# Sata.net
KiCad netlist of a schematic drawn in Altium Designer
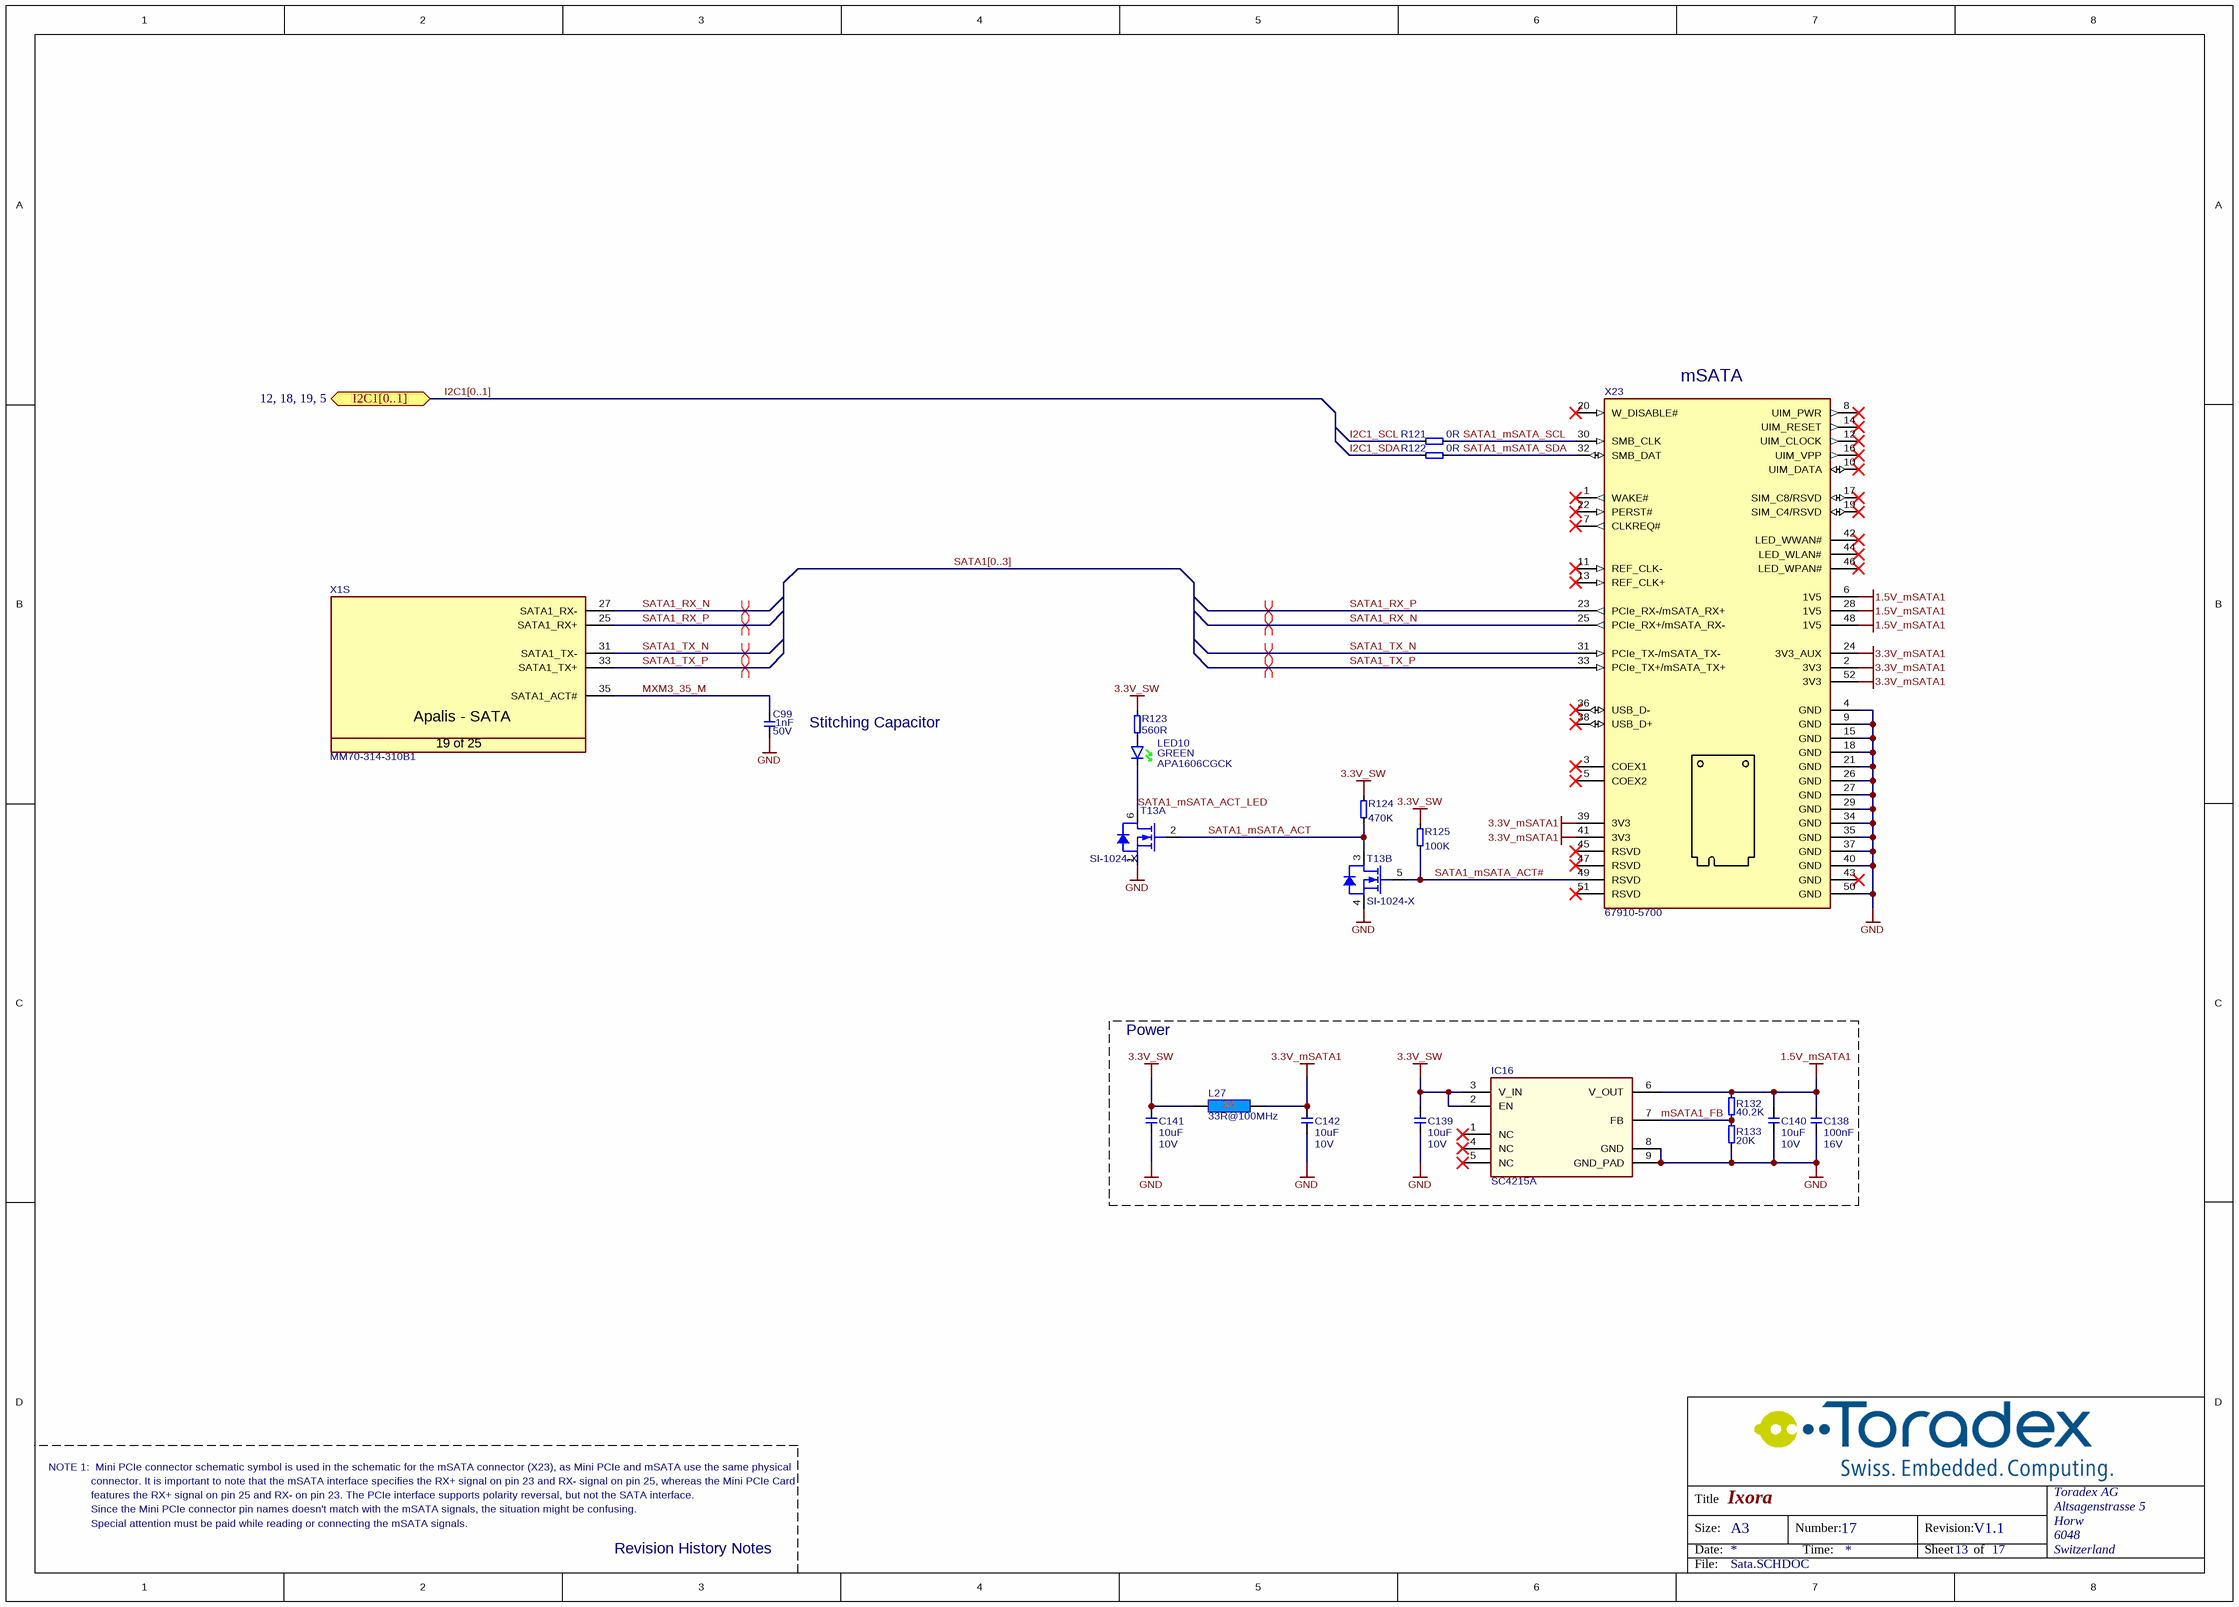
[diagram p0: Sata.SCHDOC]

(export (version "E")
  (design (tool "Eeschema 10.0.6"))
  (components
    (comp (ref "C99")
      (value "1nF")
      (footprint "CAPC1005X60N")
      (description "Capacitor Ceramic X7R 1nF 50V 10% 0402")
      (fields (field (name "TOLERANCE") "10%") (field (name "RATING") "50V"))
      (libsource (lib "Ixora") (part "C-X7R-1nF-50V-10%-0402"))
    )
    (comp (ref "C138")
      (value "100nF")
      (footprint "CAPC1005X60N")
      (description "Capacitor Ceramic X7R 100nF 16V 10% 0402")
      (fields (field (name "TOLERANCE") "10%") (field (name "RATING") "16V"))
      (libsource (lib "Ixora") (part "C-X7R-100nF-16V-10%-0402"))
    )
    (comp (ref "C139")
      (value "10uF")
      (footprint "T_CAPC0603X33N")
      (description "Capacitor Ceramic X5R 10uF 10V 20% 0603")
      (fields (field (name "TOLERANCE") "20%") (field (name "RATING") "10V"))
      (libsource (lib "Ixora") (part "C-X5R-10uF-10V-20%-0603"))
    )
    (comp (ref "C140")
      (value "10uF")
      (footprint "T_CAPC0603X33N")
      (description "Capacitor Ceramic X5R 10uF 10V 20% 0603")
      (fields (field (name "TOLERANCE") "20%") (field (name "RATING") "10V"))
      (libsource (lib "Ixora") (part "C-X5R-10uF-10V-20%-0603"))
    )
    (comp (ref "C141")
      (value "10uF")
      (footprint "T_CAPC0603X33N")
      (description "Capacitor Ceramic X5R 10uF 10V 20% 0603")
      (fields (field (name "TOLERANCE") "20%") (field (name "RATING") "10V"))
      (libsource (lib "Ixora") (part "C-X5R-10uF-10V-20%-0603"))
    )
    (comp (ref "C142")
      (value "10uF")
      (footprint "T_CAPC0603X33N")
      (description "Capacitor Ceramic X5R 10uF 10V 20% 0603")
      (fields (field (name "TOLERANCE") "20%") (field (name "RATING") "10V"))
      (libsource (lib "Ixora") (part "C-X5R-10uF-10V-20%-0603"))
    )
    (comp (ref "IC16")
      (value "IC-Semtech-SC4215A")
      (footprint "SOIC127P650X175_HS-8N")
      (description "LDO TO 2A")
      (fields (field (name "MANUFACTURER PART NO.") "SC4215A"))
      (libsource (lib "Ixora") (part "IC-Semtech-SC4215A"))
    )
    (comp (ref "L27")
      (value "33R@100MHz")
      (footprint "INDC1608X95N")
      (description "33R@100MHz 3A EMI FILTER")
      (fields (field (name "TOLERANCE") "25%"))
      (libsource (lib "Ixora") (part "L-33R@100MHz-3A-25%-0603"))
    )
    (comp (ref "LED10")
      (value "APA1606CGCK")
      (footprint "T_Kingbright_APA1606CGCK")
      (description "LED green Kingbright APA1606CGCK")
      (fields (field (name "COLOR") "GREEN") (field (name "MANUFACTURER PART NO.") "APA1606CGCK"))
      (libsource (lib "Ixora") (part "LED-Kingbright-APA1606CGCK"))
    )
    (comp (ref "R121")
      (value "0R")
      (footprint "RESC1005X40N")
      (description "Resistor 0 ohm 63mW 1% 0402")
      (fields (field (name "TOLERANCE") "1%"))
      (libsource (lib "Ixora") (part "R-0R-63mW-1%-0402"))
    )
    (comp (ref "R122")
      (value "0R")
      (footprint "RESC1005X40N")
      (description "Resistor 0 ohm 63mW 1% 0402")
      (fields (field (name "TOLERANCE") "1%"))
      (libsource (lib "Ixora") (part "R-0R-63mW-1%-0402"))
    )
    (comp (ref "R123")
      (value "560R")
      (footprint "RESC1005X40N")
      (description "Resistor 560 ohm 63mW 5% 0402")
      (fields (field (name "TOLERANCE") "5%"))
      (libsource (lib "Ixora") (part "R-560R-63mW-5%-0402"))
    )
    (comp (ref "R124")
      (value "470K")
      (footprint "RESC1005X40N")
      (description "Resistor 470 Kohm 63mW 5% 0402")
      (fields (field (name "TOLERANCE") "5%"))
      (libsource (lib "Ixora") (part "R-470KR-63mW-5%-0402"))
    )
    (comp (ref "R125")
      (value "100K")
      (footprint "RESC1005X40N")
      (description "Resistor 100 Kohm 63mW 5% 0402")
      (fields (field (name "TOLERANCE") "5%"))
      (libsource (lib "Ixora") (part "R-100KR-63mW-5%-0402"))
    )
    (comp (ref "R132")
      (value "40.2K")
      (footprint "RESC1005X40N")
      (description "Resistor 40.2 Kohm 63mW 1% 0402")
      (fields (field (name "TOLERANCE") "1%"))
      (libsource (lib "Ixora") (part "R-40.2KR-63mW-1%-0402"))
    )
    (comp (ref "R133")
      (value "20K")
      (footprint "RESC1005X40N")
      (description "Resistor 20 Kohm 63mW 1% 0402")
      (fields (field (name "TOLERANCE") "1%"))
      (libsource (lib "Ixora") (part "R-20KR-63mW-1%-0402"))
    )
    (comp (ref "T13")
      (value "T-Vishay-SI-1024X-N")
      (footprint "SOTFL50P160X60-6N")
      (description "Dual N-Channel 20V (D-S)  MOSFET")
      (fields (field (name "MANUFACTURER PART NO.") "SI-1024-X"))
      (libsource (lib "Ixora") (part "T-Vishay-SI-1024X-N"))
    )
    (comp (ref "X1")
      (value "CON-JAE-MM70-314-310B1-314-0.5mm")
      (footprint "T_JAE_MM70-314-310B1")
      (description "MXM3 Connector")
      (fields (field (name "MANUFACTURER PART NO.") "MM70-314-310B1"))
      (libsource (lib "Ixora") (part "CON-JAE-MM70-314-310B1-314-0.5mm"))
    )
    (comp (ref "X23")
      (value "67910-5700")
      (footprint "T_Molex_67910-5700")
      (description "PCIe_Mini Card Holder")
      (fields (field (name "PART NO.") "67910-5700"))
      (libsource (lib "Ixora") (part "CON-Molex-67910-5700"))
    )
  )
  (nets
    (net (code "8") (name "/I2C1_SCL") (class "Default")
      (node (ref "R121") (pin "1") (pinfunction "1_1") (pintype "passive"))
    )
    (net (code "9") (name "/I2C1_SDA") (class "Default")
      (node (ref "R122") (pin "1") (pinfunction "1_1") (pintype "passive"))
    )
    (net (code "10") (name "/MXM3_35_M") (class "Default")
      (node (ref "C99") (pin "2") (pinfunction "2_2") (pintype "passive"))
      (node (ref "X1") (pin "35") (pinfunction "SATA1_ACT#_35") (pintype "passive"))
    )
    (net (code "12") (name "/SATA1_RX_N") (class "Default")
      (node (ref "X1") (pin "27") (pinfunction "SATA1_RX-_27") (pintype "passive"))
      (node (ref "X23") (pin "25") (pinfunction "PCIe_RX+/mSATA_RX-_25") (pintype "output"))
    )
    (net (code "13") (name "/SATA1_RX_P") (class "Default")
      (node (ref "X1") (pin "25") (pinfunction "SATA1_RX+_25") (pintype "passive"))
      (node (ref "X23") (pin "23") (pinfunction "PCIe_RX-/mSATA_RX+_23") (pintype "output"))
    )
    (net (code "14") (name "/SATA1_TX_N") (class "Default")
      (node (ref "X1") (pin "31") (pinfunction "SATA1_TX-_31") (pintype "passive"))
      (node (ref "X23") (pin "31") (pinfunction "PCIe_TX-/mSATA_TX-_31") (pintype "input"))
    )
    (net (code "15") (name "/SATA1_TX_P") (class "Default")
      (node (ref "X1") (pin "33") (pinfunction "SATA1_TX+_33") (pintype "passive"))
      (node (ref "X23") (pin "33") (pinfunction "PCIe_TX+/mSATA_TX+_33") (pintype "input"))
    )
    (net (code "16") (name "/SATA1_mSATA_ACT") (class "Default")
      (node (ref "R124") (pin "2") (pinfunction "2_2") (pintype "passive"))
      (node (ref "T13") (pin "2") (pinfunction "G_2") (pintype "passive"))
      (node (ref "T13") (pin "3") (pinfunction "D_3") (pintype "passive"))
    )
    (net (code "17") (name "/SATA1_mSATA_ACT#") (class "Default")
      (node (ref "R125") (pin "1") (pinfunction "1_1") (pintype "passive"))
      (node (ref "T13") (pin "5") (pinfunction "G_5") (pintype "passive"))
      (node (ref "X23") (pin "49") (pinfunction "RSVD_49") (pintype "passive"))
    )
    (net (code "18") (name "/SATA1_mSATA_ACT_LED") (class "Default")
      (node (ref "LED10") (pin "1") (pinfunction "K_1") (pintype "passive"))
      (node (ref "T13") (pin "6") (pinfunction "D_6") (pintype "passive"))
    )
    (net (code "19") (name "/SATA1_mSATA_SCL") (class "Default")
      (node (ref "R121") (pin "2") (pinfunction "2_2") (pintype "passive"))
      (node (ref "X23") (pin "30") (pinfunction "SMB_CLK_30") (pintype "input"))
    )
    (net (code "20") (name "/SATA1_mSATA_SDA") (class "Default")
      (node (ref "R122") (pin "2") (pinfunction "2_2") (pintype "passive"))
      (node (ref "X23") (pin "32") (pinfunction "SMB_DAT_32") (pintype "bidirectional"))
    )
    (net (code "21") (name "/mSATA1_FB") (class "Default")
      (node (ref "IC16") (pin "7") (pinfunction "FB_7") (pintype "passive"))
      (node (ref "R132") (pin "1") (pinfunction "1_1") (pintype "passive"))
      (node (ref "R133") (pin "2") (pinfunction "2_2") (pintype "passive"))
    )
    (net (code "22") (name "1.5V_mSATA1") (class "Default")
      (node (ref "C138") (pin "2") (pinfunction "2_2") (pintype "passive"))
      (node (ref "C140") (pin "2") (pinfunction "2_2") (pintype "passive"))
      (node (ref "IC16") (pin "6") (pinfunction "V_OUT_6") (pintype "passive"))
      (node (ref "R132") (pin "2") (pinfunction "2_2") (pintype "passive"))
      (node (ref "X23") (pin "28") (pinfunction "1V5_28") (pintype "power_in"))
      (node (ref "X23") (pin "48") (pinfunction "1V5_48") (pintype "power_in"))
      (node (ref "X23") (pin "6") (pinfunction "1V5_6") (pintype "power_in"))
    )
    (net (code "23") (name "3.3V_SW") (class "Default")
      (node (ref "C139") (pin "2") (pinfunction "2_2") (pintype "passive"))
      (node (ref "C141") (pin "2") (pinfunction "2_2") (pintype "passive"))
      (node (ref "IC16") (pin "2") (pinfunction "EN_2") (pintype "passive"))
      (node (ref "IC16") (pin "3") (pinfunction "V_IN_3") (pintype "passive"))
      (node (ref "L27") (pin "1") (pinfunction "1_1") (pintype "passive"))
      (node (ref "R123") (pin "1") (pinfunction "1_1") (pintype "passive"))
      (node (ref "R124") (pin "1") (pinfunction "1_1") (pintype "passive"))
      (node (ref "R125") (pin "2") (pinfunction "2_2") (pintype "passive"))
    )
    (net (code "24") (name "3.3V_mSATA1") (class "Default")
      (node (ref "C142") (pin "2") (pinfunction "2_2") (pintype "passive"))
      (node (ref "L27") (pin "2") (pinfunction "2_2") (pintype "passive"))
      (node (ref "X23") (pin "2") (pinfunction "3V3_2") (pintype "power_in"))
      (node (ref "X23") (pin "24") (pinfunction "3V3_AUX_24") (pintype "power_in"))
      (node (ref "X23") (pin "39") (pinfunction "3V3_39") (pintype "passive"))
      (node (ref "X23") (pin "41") (pinfunction "3V3_41") (pintype "passive"))
      (node (ref "X23") (pin "52") (pinfunction "3V3_52") (pintype "power_in"))
    )
    (net (code "25") (name "GND") (class "Default")
      (node (ref "C138") (pin "1") (pinfunction "1_1") (pintype "passive"))
      (node (ref "C139") (pin "1") (pinfunction "1_1") (pintype "passive"))
      (node (ref "C140") (pin "1") (pinfunction "1_1") (pintype "passive"))
      (node (ref "C141") (pin "1") (pinfunction "1_1") (pintype "passive"))
      (node (ref "C142") (pin "1") (pinfunction "1_1") (pintype "passive"))
      (node (ref "C99") (pin "1") (pinfunction "1_1") (pintype "passive"))
      (node (ref "IC16") (pin "8") (pinfunction "GND_8") (pintype "passive"))
      (node (ref "IC16") (pin "9") (pinfunction "GND_PAD_9") (pintype "passive"))
      (node (ref "R133") (pin "1") (pinfunction "1_1") (pintype "passive"))
      (node (ref "T13") (pin "1") (pinfunction "S_1") (pintype "passive"))
      (node (ref "T13") (pin "4") (pinfunction "S_4") (pintype "passive"))
      (node (ref "X23") (pin "15") (pinfunction "GND_15") (pintype "power_in"))
      (node (ref "X23") (pin "18") (pinfunction "GND_18") (pintype "power_in"))
      (node (ref "X23") (pin "21") (pinfunction "GND_21") (pintype "power_in"))
      (node (ref "X23") (pin "26") (pinfunction "GND_26") (pintype "power_in"))
      (node (ref "X23") (pin "27") (pinfunction "GND_27") (pintype "power_in"))
      (node (ref "X23") (pin "29") (pinfunction "GND_29") (pintype "power_in"))
      (node (ref "X23") (pin "34") (pinfunction "GND_34") (pintype "power_in"))
      (node (ref "X23") (pin "35") (pinfunction "GND_35") (pintype "power_in"))
      (node (ref "X23") (pin "37") (pinfunction "GND_37") (pintype "power_in"))
      (node (ref "X23") (pin "4") (pinfunction "GND_4") (pintype "power_in"))
      (node (ref "X23") (pin "40") (pinfunction "GND_40") (pintype "power_in"))
      (node (ref "X23") (pin "50") (pinfunction "GND_50") (pintype "power_in"))
      (node (ref "X23") (pin "9") (pinfunction "GND_9") (pintype "power_in"))
    )
    (net (code "26") (name "Net-(LED10-A)") (class "Default")
      (node (ref "LED10") (pin "2") (pinfunction "A_2") (pintype "passive"))
      (node (ref "R123") (pin "2") (pinfunction "2_2") (pintype "passive"))
    )
    (net (code "27") (name "unconnected-(IC16-NC-Pad1)") (class "Default")
      (node (ref "IC16") (pin "1") (pinfunction "NC_1") (pintype "passive+no_connect"))
    )
    (net (code "28") (name "unconnected-(IC16-NC-Pad4)") (class "Default")
      (node (ref "IC16") (pin "4") (pinfunction "NC_4") (pintype "passive+no_connect"))
    )
    (net (code "29") (name "unconnected-(IC16-NC-Pad5)") (class "Default")
      (node (ref "IC16") (pin "5") (pinfunction "NC_5") (pintype "passive+no_connect"))
    )
    (net (code "30") (name "unconnected-(X23-CLKREQ#-Pad7)") (class "Default")
      (node (ref "X23") (pin "7") (pinfunction "CLKREQ#_7") (pintype "output+no_connect"))
    )
    (net (code "31") (name "unconnected-(X23-COEX1-Pad3)") (class "Default")
      (node (ref "X23") (pin "3") (pinfunction "COEX1_3") (pintype "passive+no_connect"))
    )
    (net (code "32") (name "unconnected-(X23-COEX2-Pad5)") (class "Default")
      (node (ref "X23") (pin "5") (pinfunction "COEX2_5") (pintype "passive+no_connect"))
    )
    (net (code "33") (name "unconnected-(X23-GND-Pad43)") (class "Default")
      (node (ref "X23") (pin "43") (pinfunction "GND_43") (pintype "power_in+no_connect"))
    )
    (net (code "34") (name "unconnected-(X23-LED_WLAN#-Pad44)") (class "Default")
      (node (ref "X23") (pin "44") (pinfunction "LED_WLAN#_44") (pintype "open_collector+no_connect"))
    )
    (net (code "35") (name "unconnected-(X23-LED_WPAN#-Pad46)") (class "Default")
      (node (ref "X23") (pin "46") (pinfunction "LED_WPAN#_46") (pintype "open_collector+no_connect"))
    )
    (net (code "36") (name "unconnected-(X23-LED_WWAN#-Pad42)") (class "Default")
      (node (ref "X23") (pin "42") (pinfunction "LED_WWAN#_42") (pintype "open_collector+no_connect"))
    )
    (net (code "37") (name "unconnected-(X23-PERST#-Pad22)") (class "Default")
      (node (ref "X23") (pin "22") (pinfunction "PERST#_22") (pintype "input+no_connect"))
    )
    (net (code "38") (name "unconnected-(X23-REF_CLK+-Pad13)") (class "Default")
      (node (ref "X23") (pin "13") (pinfunction "REF_CLK+_13") (pintype "input+no_connect"))
    )
    (net (code "39") (name "unconnected-(X23-REF_CLK--Pad11)") (class "Default")
      (node (ref "X23") (pin "11") (pinfunction "REF_CLK-_11") (pintype "input+no_connect"))
    )
    (net (code "40") (name "unconnected-(X23-RSVD-Pad45)") (class "Default")
      (node (ref "X23") (pin "45") (pinfunction "RSVD_45") (pintype "passive+no_connect"))
    )
    (net (code "41") (name "unconnected-(X23-RSVD-Pad47)") (class "Default")
      (node (ref "X23") (pin "47") (pinfunction "RSVD_47") (pintype "passive+no_connect"))
    )
    (net (code "42") (name "unconnected-(X23-RSVD-Pad51)") (class "Default")
      (node (ref "X23") (pin "51") (pinfunction "RSVD_51") (pintype "passive+no_connect"))
    )
    (net (code "43") (name "unconnected-(X23-SIM_C4{slash}RSVD-Pad19)") (class "Default")
      (node (ref "X23") (pin "19") (pinfunction "SIM_C4/RSVD_19") (pintype "bidirectional+no_connect"))
    )
    (net (code "44") (name "unconnected-(X23-SIM_C8{slash}RSVD-Pad17)") (class "Default")
      (node (ref "X23") (pin "17") (pinfunction "SIM_C8/RSVD_17") (pintype "bidirectional+no_connect"))
    )
    (net (code "45") (name "unconnected-(X23-UIM_CLOCK-Pad12)") (class "Default")
      (node (ref "X23") (pin "12") (pinfunction "UIM_CLOCK_12") (pintype "output+no_connect"))
    )
    (net (code "46") (name "unconnected-(X23-UIM_DATA-Pad10)") (class "Default")
      (node (ref "X23") (pin "10") (pinfunction "UIM_DATA_10") (pintype "bidirectional+no_connect"))
    )
    (net (code "47") (name "unconnected-(X23-UIM_PWR-Pad8)") (class "Default")
      (node (ref "X23") (pin "8") (pinfunction "UIM_PWR_8") (pintype "output+no_connect"))
    )
    (net (code "48") (name "unconnected-(X23-UIM_RESET-Pad14)") (class "Default")
      (node (ref "X23") (pin "14") (pinfunction "UIM_RESET_14") (pintype "output+no_connect"))
    )
    (net (code "49") (name "unconnected-(X23-UIM_VPP-Pad16)") (class "Default")
      (node (ref "X23") (pin "16") (pinfunction "UIM_VPP_16") (pintype "output+no_connect"))
    )
    (net (code "50") (name "unconnected-(X23-USB_D+-Pad38)") (class "Default")
      (node (ref "X23") (pin "38") (pinfunction "USB_D+_38") (pintype "bidirectional+no_connect"))
    )
    (net (code "51") (name "unconnected-(X23-USB_D--Pad36)") (class "Default")
      (node (ref "X23") (pin "36") (pinfunction "USB_D-_36") (pintype "bidirectional+no_connect"))
    )
    (net (code "52") (name "unconnected-(X23-WAKE#-Pad1)") (class "Default")
      (node (ref "X23") (pin "1") (pinfunction "WAKE#_1") (pintype "output+no_connect"))
    )
    (net (code "53") (name "unconnected-(X23-W_DISABLE#-Pad20)") (class "Default")
      (node (ref "X23") (pin "20") (pinfunction "W_DISABLE#_20") (pintype "input+no_connect"))
    )
  )
)
